# brain_rev_102.net
KiCad netlist of a schematic drawn in EAGLE
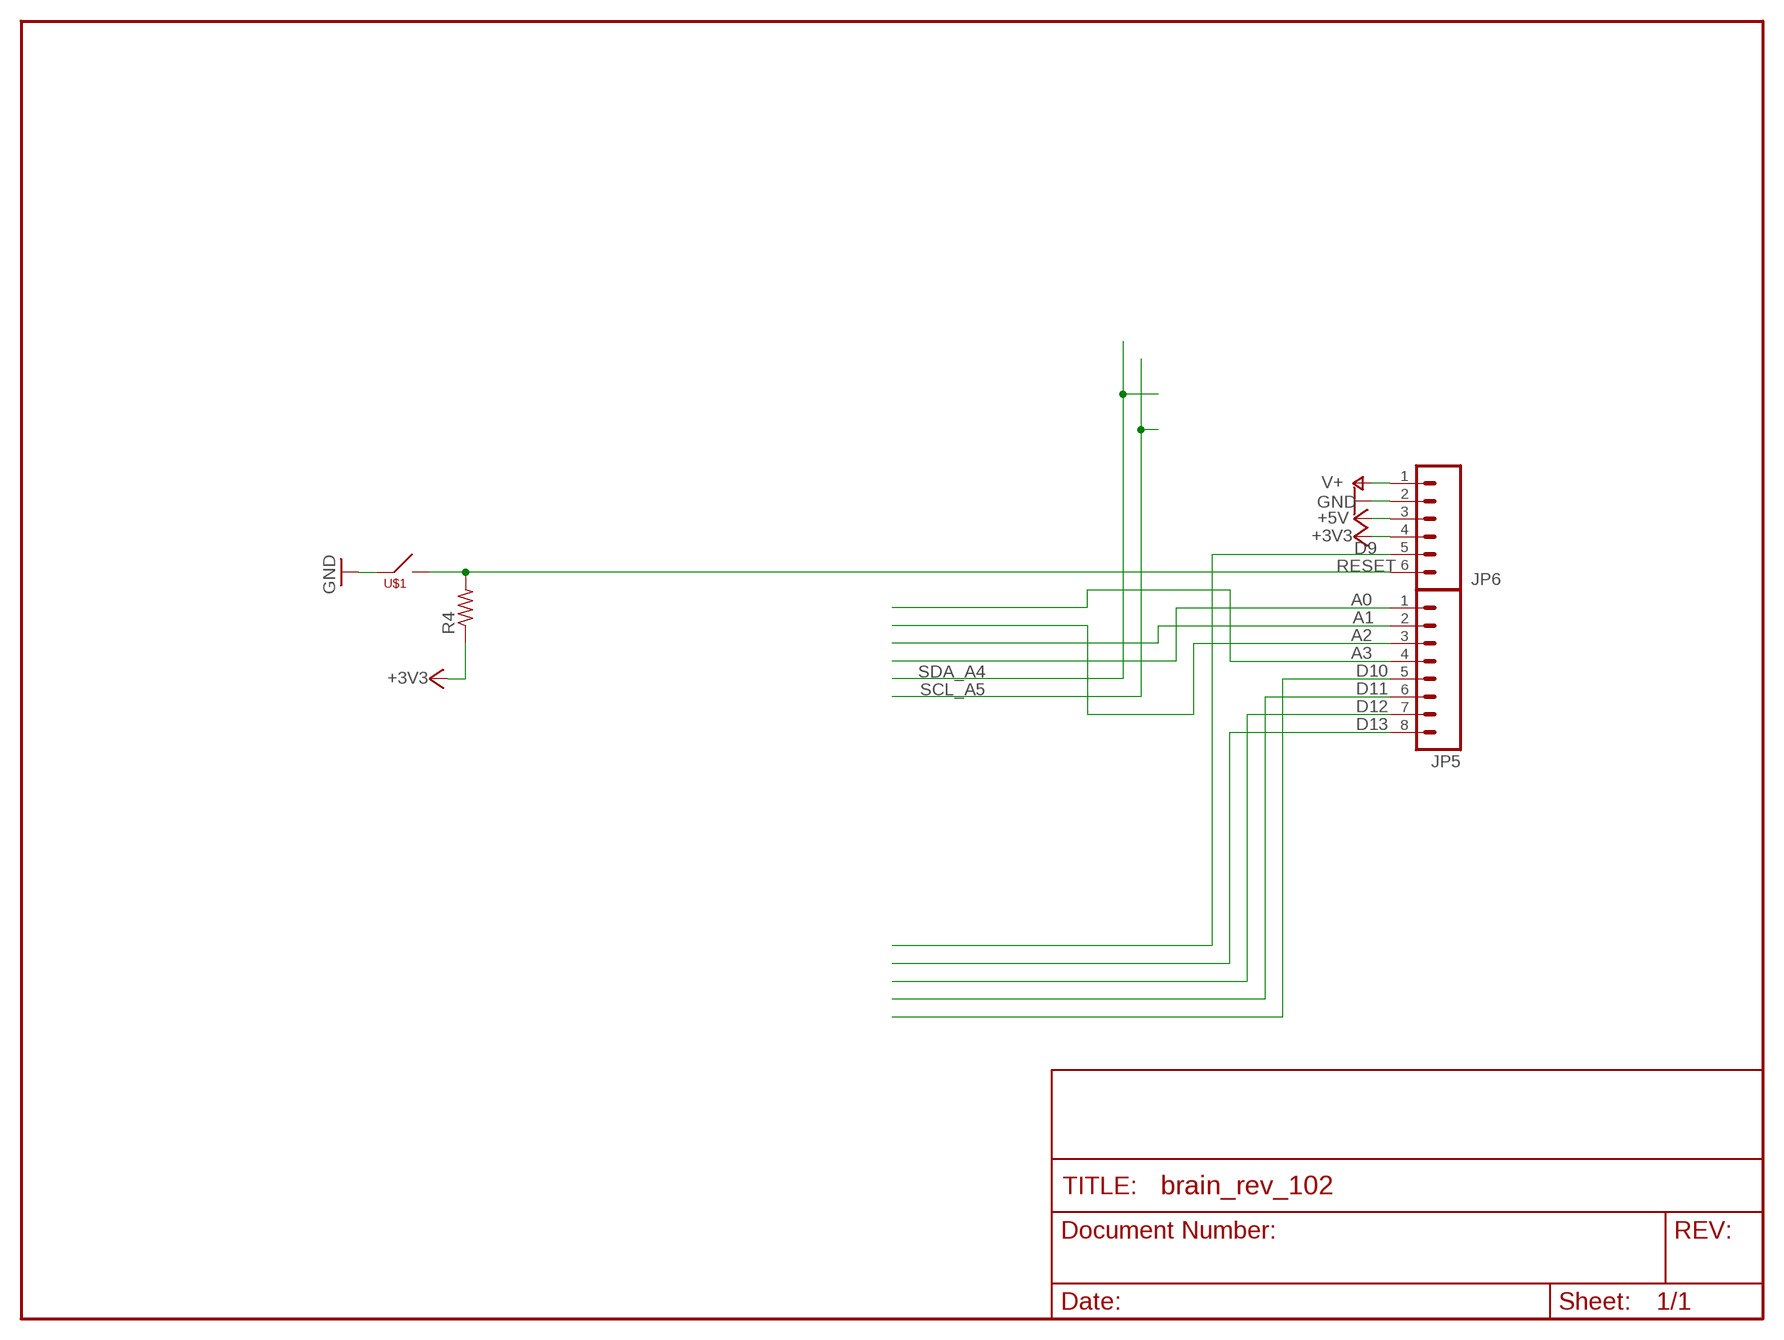
[diagram p0: schematic, sheet 1]

(export (version "E")
  (design (tool "Eeschema 10.0.6"))
  (components
    (comp (ref "JP5")
      (value "M081X08")
      (footprint "eagle-import:1X08")
      (libsource (lib "eagle-import") (part "M081X08"))
    )
    (comp (ref "JP6")
      (value "M06SIP")
      (footprint "eagle-import:1X06")
      (libsource (lib "eagle-import") (part "M06SIP"))
    )
    (comp (ref "R4")
      (value "R-US_0204/2V")
      (footprint "eagle-import:0204V")
      (libsource (lib "eagle-import") (part "R-US_0204/2V"))
    )
    (comp (ref "U$1")
      (value "PTS635_SWITCH")
      (footprint "eagle-import:PTS635_SWITCH")
      (libsource (lib "eagle-import") (part "PTS635_SWITCH"))
    )
  )
  (nets
    (net (code "1") (name "+3V3") (class "Default")
      (node (ref "JP6") (pin "4") (pinfunction "4_4") (pintype "passive"))
      (node (ref "R4") (pin "1") (pinfunction "1_1") (pintype "passive"))
    )
    (net (code "2") (name "+5V") (class "Default")
      (node (ref "JP6") (pin "3") (pinfunction "3_3") (pintype "passive"))
    )
    (net (code "3") (name "/A0") (class "Default")
      (node (ref "JP5") (pin "4") (pinfunction "4_4") (pintype "passive"))
    )
    (net (code "4") (name "/A1") (class "Default")
      (node (ref "JP5") (pin "3") (pinfunction "3_3") (pintype "passive"))
    )
    (net (code "5") (name "/A2") (class "Default")
      (node (ref "JP5") (pin "2") (pinfunction "2_2") (pintype "passive"))
    )
    (net (code "6") (name "/A3") (class "Default")
      (node (ref "JP5") (pin "1") (pinfunction "1_1") (pintype "passive"))
    )
    (net (code "7") (name "/D9") (class "Default")
      (node (ref "JP6") (pin "5") (pinfunction "5_5") (pintype "passive"))
    )
    (net (code "8") (name "/D10") (class "Default")
      (node (ref "JP5") (pin "8") (pinfunction "8_8") (pintype "passive"))
    )
    (net (code "9") (name "/D11") (class "Default")
      (node (ref "JP5") (pin "7") (pinfunction "7_7") (pintype "passive"))
    )
    (net (code "10") (name "/D12") (class "Default")
      (node (ref "JP5") (pin "6") (pinfunction "6_6") (pintype "passive"))
    )
    (net (code "11") (name "/D13") (class "Default")
      (node (ref "JP5") (pin "5") (pinfunction "5_5") (pintype "passive"))
    )
    (net (code "12") (name "/RESET") (class "Default")
      (node (ref "JP6") (pin "6") (pinfunction "6_6") (pintype "passive"))
      (node (ref "R4") (pin "2") (pinfunction "2_2") (pintype "passive"))
      (node (ref "U$1") (pin "P$2") (pinfunction "P$2_P$2") (pintype "bidirectional"))
    )
    (net (code "15") (name "GND") (class "Default")
      (node (ref "JP6") (pin "2") (pinfunction "2_2") (pintype "passive"))
      (node (ref "U$1") (pin "P$1") (pinfunction "P$1_P$1") (pintype "bidirectional"))
    )
    (net (code "16") (name "V+") (class "Default")
      (node (ref "JP6") (pin "1") (pinfunction "1_1") (pintype "passive"))
    )
  )
)
